# L298.net
KiCad netlist of a schematic drawn in Altium Designer
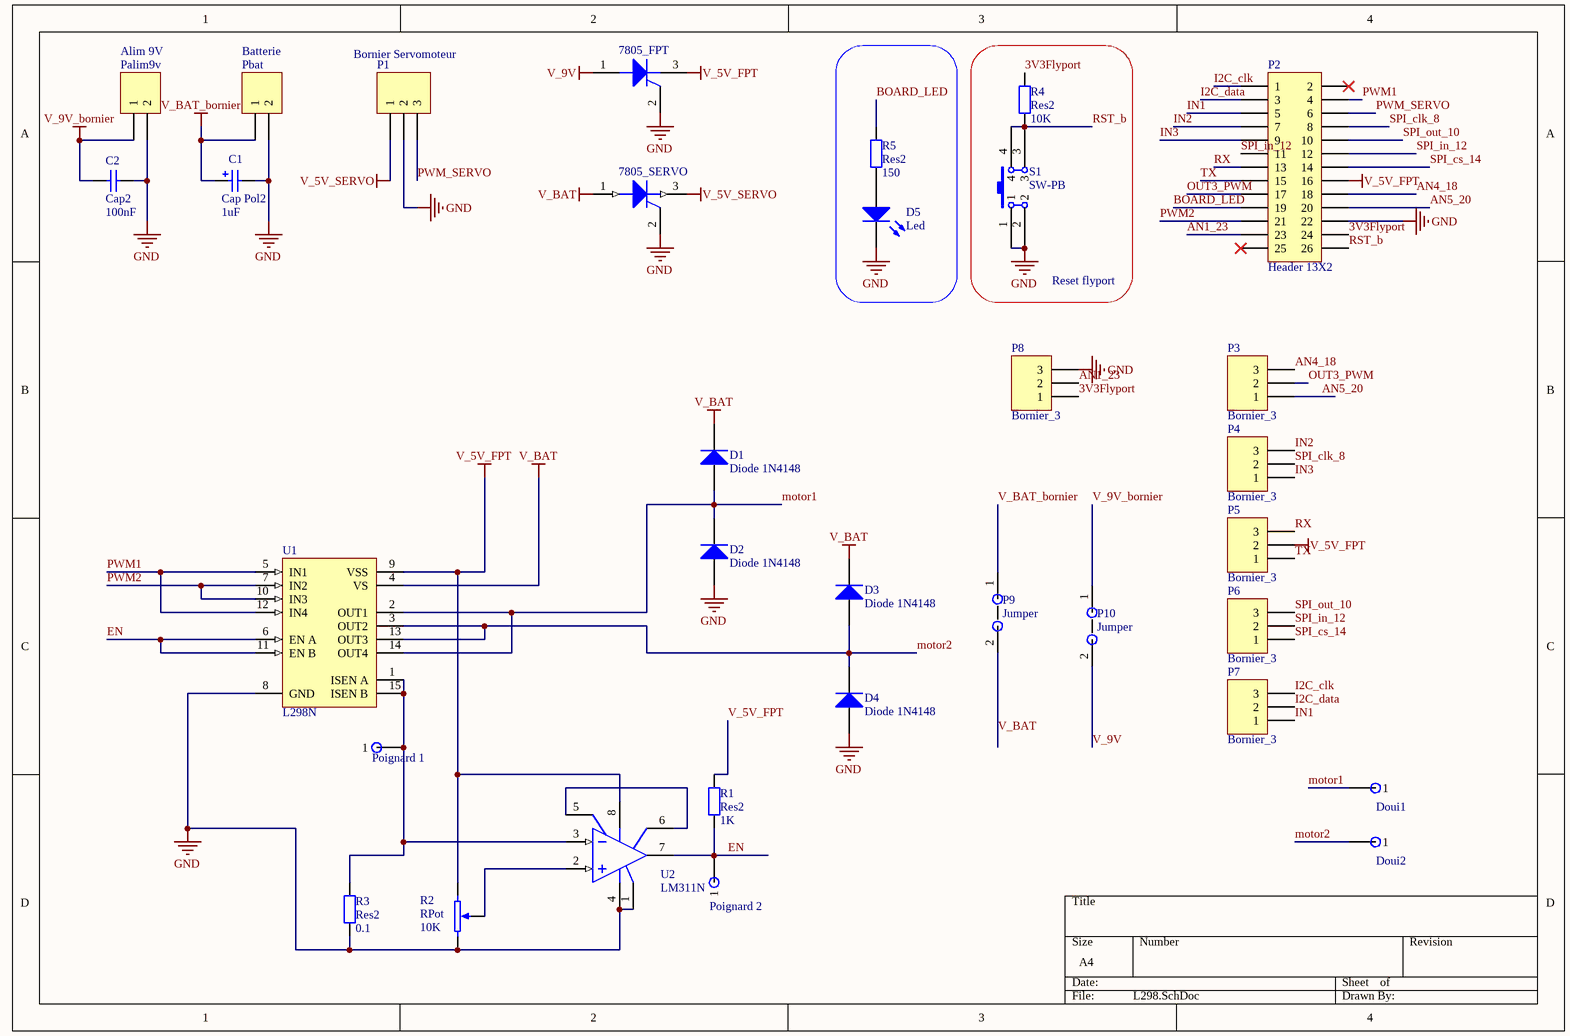
[diagram p0: L298.SchDoc]

(export (version "E")
  (design (tool "Eeschema 10.0.6"))
  (components
    (comp (ref "7805_FPT")
      (value "SCR")
      (footprint "TO-220-AB")
      (description "Silicon Controlled Rectifier")
      (fields (field (name "PUBLISHER") "Altium Limited"))
      (libsource (lib "Miscellaneous Devices") (part "SCR"))
    )
    (comp (ref "7805_SERVO")
      (value "SCR")
      (footprint "TO-220-AB")
      (description "Silicon Controlled Rectifier")
      (fields (field (name "PUBLISHER") "Altium Limited"))
      (libsource (lib "Miscellaneous Devices") (part "SCR"))
    )
    (comp (ref "C1")
      (value "Cap Pol2")
      (footprint "Capa2_pol")
      (description "Polarized Capacitor (Radial)")
      (fields (field (name "ALTIUM_VALUE") "1uF") (field (name "PUBLISHER") "Altium Limited"))
      (libsource (lib "LIBRAIRIE_INTEGREE_PHELMA1") (part "Cap Pol2"))
    )
    (comp (ref "C2")
      (value "Cap2")
      (footprint "CAPA2")
      (description "Capacitor")
      (fields (field (name "ALTIUM_VALUE") "100nF") (field (name "PUBLISHER") "Altium Limited"))
      (libsource (lib "LIBRAIRIE_INTEGREE_PHELMA1") (part "Cap2"))
    )
    (comp (ref "D1")
      (value "Diode 1N4148")
      (footprint "Ddiode")
      (description "High Conductance Fast Diode")
      (fields (field (name "PUBLISHER") "Altium Limited"))
      (libsource (lib "LIBRAIRIE_INTEGREE_PHELMA1") (part "Diode 1N4148"))
    )
    (comp (ref "D2")
      (value "Diode 1N4148")
      (footprint "Ddiode")
      (description "High Conductance Fast Diode")
      (fields (field (name "PUBLISHER") "Altium Limited"))
      (libsource (lib "LIBRAIRIE_INTEGREE_PHELMA1") (part "Diode 1N4148"))
    )
    (comp (ref "D3")
      (value "Diode 1N4148")
      (footprint "Ddiode")
      (description "High Conductance Fast Diode")
      (fields (field (name "PUBLISHER") "Altium Limited"))
      (libsource (lib "LIBRAIRIE_INTEGREE_PHELMA1") (part "Diode 1N4148"))
    )
    (comp (ref "D4")
      (value "Diode 1N4148")
      (footprint "Ddiode")
      (description "High Conductance Fast Diode")
      (fields (field (name "PUBLISHER") "Altium Limited"))
      (libsource (lib "LIBRAIRIE_INTEGREE_PHELMA1") (part "Diode 1N4148"))
    )
    (comp (ref "D5")
      (value "Led")
      (footprint "LED")
      (description "LED")
      (fields (field (name "PUBLISHER") "Altium Limited"))
      (libsource (lib "LIBRAIRIE_INTEGREE_PHELMA1") (part "Led"))
    )
    (comp (ref "Doui1")
      (value "douille_2mm")
      (footprint "Douille-2mm")
      (description "1-Pin")
      (fields (field (name "PUBLISHER") "Altium Limited"))
      (libsource (lib "INTEGRATED_LIBRARY1_CONNECTEURS") (part "douille_2mm"))
    )
    (comp (ref "Doui2")
      (value "douille_2mm")
      (footprint "Douille-2mm")
      (description "1-Pin")
      (fields (field (name "PUBLISHER") "Altium Limited"))
      (libsource (lib "INTEGRATED_LIBRARY1_CONNECTEURS") (part "douille_2mm"))
    )
    (comp (ref "P1")
      (value "Bornier Servomoteur")
      (footprint "Bornier_3")
      (description "Header, 3-Pin")
      (fields (field (name "PUBLISHER") "Altium Limited"))
      (libsource (lib "") (part "Bornier_3_1"))
    )
    (comp (ref "P2")
      (value "Header 13X2")
      (footprint "HDR2X13")
      (description "Header, 13-Pin, Dual row")
      (fields (field (name "PUBLISHER") "Altium Limited"))
      (libsource (lib "Miscellaneous Connectors") (part "Header 13X2"))
    )
    (comp (ref "P3")
      (value "Bornier_3")
      (footprint "Bornier_3")
      (description "Header, 3-Pin")
      (fields (field (name "PUBLISHER") "Altium Limited"))
      (libsource (lib "INTEGRATED_LIBRARY1_CONNECTEURS") (part "Bornier_3"))
    )
    (comp (ref "P4")
      (value "Bornier_3")
      (footprint "Bornier_3")
      (description "Header, 3-Pin")
      (fields (field (name "PUBLISHER") "Altium Limited"))
      (libsource (lib "INTEGRATED_LIBRARY1_CONNECTEURS") (part "Bornier_3"))
    )
    (comp (ref "P5")
      (value "Bornier_3")
      (footprint "Bornier_3")
      (description "Header, 3-Pin")
      (fields (field (name "PUBLISHER") "Altium Limited"))
      (libsource (lib "INTEGRATED_LIBRARY1_CONNECTEURS") (part "Bornier_3"))
    )
    (comp (ref "P6")
      (value "Bornier_3")
      (footprint "Bornier_3")
      (description "Header, 3-Pin")
      (fields (field (name "PUBLISHER") "Altium Limited"))
      (libsource (lib "INTEGRATED_LIBRARY1_CONNECTEURS") (part "Bornier_3"))
    )
    (comp (ref "P7")
      (value "Bornier_3")
      (footprint "Bornier_3")
      (description "Header, 3-Pin")
      (fields (field (name "PUBLISHER") "Altium Limited"))
      (libsource (lib "INTEGRATED_LIBRARY1_CONNECTEURS") (part "Bornier_3"))
    )
    (comp (ref "P8")
      (value "Bornier_3")
      (footprint "Bornier_3")
      (description "Header, 3-Pin")
      (fields (field (name "PUBLISHER") "Altium Limited"))
      (libsource (lib "INTEGRATED_LIBRARY1_CONNECTEURS") (part "Bornier_3"))
    )
    (comp (ref "P9")
      (value "Jumper")
      (footprint "picot2")
      (fields (field (name "PUBLISHER") "Altium Limited"))
      (libsource (lib "INTEGRATED_LIBRARY1_CONNECTEURS") (part "Jumper"))
    )
    (comp (ref "P10")
      (value "Jumper")
      (footprint "picot2")
      (fields (field (name "PUBLISHER") "Altium Limited"))
      (libsource (lib "INTEGRATED_LIBRARY1_CONNECTEURS") (part "Jumper"))
    )
    (comp (ref "Palim9v")
      (value "Alim 9V")
      (footprint "Bornier_2")
      (description "Header, 2-Pin")
      (fields (field (name "PUBLISHER") "Altium Limited"))
      (libsource (lib "INTEGRATED_LIBRARY1_CONNECTEURS") (part "Bornier_2"))
    )
    (comp (ref "Pbat")
      (value "Batterie")
      (footprint "Bornier_2")
      (description "Header, 2-Pin")
      (fields (field (name "PUBLISHER") "Altium Limited"))
      (libsource (lib "INTEGRATED_LIBRARY1_CONNECTEURS") (part "Bornier_2"))
    )
    (comp (ref "Poignard 1")
      (value "Poignard")
      (footprint "Poignard")
      (fields (field (name "PUBLISHER") "Altium Limited"))
      (libsource (lib "INTEGRATED_LIBRARY1_CONNECTEURS") (part "Poignard"))
    )
    (comp (ref "Poignard 2")
      (value "Poignard")
      (footprint "Poignard")
      (fields (field (name "PUBLISHER") "Altium Limited"))
      (libsource (lib "INTEGRATED_LIBRARY1_CONNECTEURS") (part "Poignard"))
    )
    (comp (ref "R1")
      (value "Res2")
      (footprint "res5_1/4W")
      (description "Resistor")
      (fields (field (name "ALTIUM_VALUE") "1K") (field (name "PUBLISHER") "Altium Limited"))
      (libsource (lib "") (part "Res2_1"))
    )
    (comp (ref "R2")
      (value "RPot")
      (footprint "AJUSTABLE")
      (description "Potentiometer")
      (fields (field (name "ALTIUM_VALUE") "10K") (field (name "PUBLISHER") "Altium Limited"))
      (libsource (lib "LIBRAIRIE_INTEGREE_PHELMA1") (part "RPot"))
    )
    (comp (ref "R3")
      (value "Res2")
      (footprint "res5_1/4W")
      (description "Resistor")
      (fields (field (name "ALTIUM_VALUE") "0.1") (field (name "PUBLISHER") "Altium Limited"))
      (libsource (lib "LIBRAIRIE_INTEGREE_PHELMA1") (part "Res2"))
    )
    (comp (ref "R4")
      (value "Res2")
      (footprint "res5_1/4W")
      (description "Resistor")
      (fields (field (name "ALTIUM_VALUE") "10K") (field (name "PUBLISHER") "Altium Limited"))
      (libsource (lib "LIBRAIRIE_INTEGREE_PHELMA1") (part "Res2"))
    )
    (comp (ref "R5")
      (value "Res2")
      (footprint "res5_1/4W")
      (description "Resistor")
      (fields (field (name "ALTIUM_VALUE") "150") (field (name "PUBLISHER") "Altium Limited"))
      (libsource (lib "LIBRAIRIE_INTEGREE_PHELMA1") (part "Res2"))
    )
    (comp (ref "S1")
      (value "SW-PB")
      (footprint "SW_BP")
      (description "Switch")
      (fields (field (name "PUBLISHER") "Altium Limited"))
      (libsource (lib "INTEGRATED_LIBRARY1_CONNECTEURS") (part "SW-PB"))
    )
    (comp (ref "U1")
      (value "L298N")
      (footprint "Multiwatt15V")
      (description "Dual Full Bridge Driver")
      (fields (field (name "PUBLISHER") "Altium Limited"))
      (libsource (lib "ST Interface DC Motor Controller") (part "L298N"))
    )
    (comp (ref "U2")
      (value "LM311N")
      (footprint "LIBRAIRIE_INTEGREE_PHELMA1:DIP8")
      (description "Voltage Comparator")
      (fields (field (name "PUBLISHER") "Altium Limited"))
      (libsource (lib "LIBRAIRIE_INTEGREE_PHELMA1") (part "LM311N"))
    )
  )
  (nets
    (net (code "1") (name "/3V3Flyport") (class "Default")
      (node (ref "P2") (pin "24") (pinfunction "24_24") (pintype "passive"))
      (node (ref "P8") (pin "1") (pinfunction "1_1") (pintype "passive"))
      (node (ref "R4") (pin "1") (pinfunction "1_1") (pintype "passive"))
    )
    (net (code "2") (name "/AN1_23") (class "Default")
      (node (ref "P2") (pin "23") (pinfunction "23_23") (pintype "passive"))
      (node (ref "P8") (pin "2") (pinfunction "2_2") (pintype "passive"))
    )
    (net (code "3") (name "/AN4_18") (class "Default")
      (node (ref "P2") (pin "18") (pinfunction "18_18") (pintype "passive"))
      (node (ref "P3") (pin "3") (pinfunction "3_3") (pintype "passive"))
    )
    (net (code "4") (name "/AN5_20") (class "Default")
      (node (ref "P2") (pin "20") (pinfunction "20_20") (pintype "passive"))
      (node (ref "P3") (pin "1") (pinfunction "1_1") (pintype "passive"))
    )
    (net (code "5") (name "/BOARD_LED") (class "Default")
      (node (ref "P2") (pin "19") (pinfunction "19_19") (pintype "passive"))
      (node (ref "R5") (pin "1") (pinfunction "1_1") (pintype "passive"))
    )
    (net (code "6") (name "/EN") (class "Default")
      (node (ref "Poignard 2") (pin "1") (pinfunction "1_1") (pintype "passive"))
      (node (ref "R1") (pin "1") (pinfunction "1_1") (pintype "passive"))
      (node (ref "U1") (pin "11") (pinfunction "EN_B_11") (pintype "input"))
      (node (ref "U1") (pin "6") (pinfunction "EN_A_6") (pintype "input"))
      (node (ref "U2") (pin "7") (pinfunction "OUT_7") (pintype "open_collector"))
    )
    (net (code "7") (name "/I2C_clk") (class "Default")
      (node (ref "P2") (pin "1") (pinfunction "1_1") (pintype "passive"))
      (node (ref "P7") (pin "3") (pinfunction "3_3") (pintype "passive"))
    )
    (net (code "8") (name "/I2C_data") (class "Default")
      (node (ref "P2") (pin "3") (pinfunction "3_3") (pintype "passive"))
      (node (ref "P7") (pin "2") (pinfunction "2_2") (pintype "passive"))
    )
    (net (code "9") (name "/IN1") (class "Default")
      (node (ref "P2") (pin "5") (pinfunction "5_5") (pintype "passive"))
      (node (ref "P7") (pin "1") (pinfunction "1_1") (pintype "passive"))
    )
    (net (code "10") (name "/IN2") (class "Default")
      (node (ref "P2") (pin "7") (pinfunction "7_7") (pintype "passive"))
      (node (ref "P4") (pin "3") (pinfunction "3_3") (pintype "passive"))
    )
    (net (code "11") (name "/IN3") (class "Default")
      (node (ref "P2") (pin "9") (pinfunction "9_9") (pintype "passive"))
      (node (ref "P4") (pin "1") (pinfunction "1_1") (pintype "passive"))
    )
    (net (code "12") (name "/OUT3_PWM") (class "Default")
      (node (ref "P2") (pin "17") (pinfunction "17_17") (pintype "passive"))
      (node (ref "P3") (pin "2") (pinfunction "2_2") (pintype "passive"))
    )
    (net (code "13") (name "/PWM1") (class "Default")
      (node (ref "P2") (pin "4") (pinfunction "4_4") (pintype "passive"))
      (node (ref "U1") (pin "12") (pinfunction "IN4_12") (pintype "input"))
      (node (ref "U1") (pin "5") (pinfunction "IN1_5") (pintype "input"))
    )
    (net (code "14") (name "/PWM2") (class "Default")
      (node (ref "P2") (pin "21") (pinfunction "21_21") (pintype "passive"))
      (node (ref "U1") (pin "10") (pinfunction "IN3_10") (pintype "input"))
      (node (ref "U1") (pin "7") (pinfunction "IN2_7") (pintype "input"))
    )
    (net (code "15") (name "/PWM_SERVO") (class "Default")
      (node (ref "P1") (pin "3") (pinfunction "3_3") (pintype "passive"))
      (node (ref "P2") (pin "6") (pinfunction "6_6") (pintype "passive"))
    )
    (net (code "16") (name "/RST_b") (class "Default")
      (node (ref "P2") (pin "26") (pinfunction "26_26") (pintype "passive"))
      (node (ref "R4") (pin "2") (pinfunction "2_2") (pintype "passive"))
      (node (ref "S1") (pin "3") (pinfunction "3_3") (pintype "passive"))
      (node (ref "S1") (pin "4") (pinfunction "4_4") (pintype "passive"))
    )
    (net (code "17") (name "/RX") (class "Default")
      (node (ref "P2") (pin "13") (pinfunction "13_13") (pintype "passive"))
      (node (ref "P5") (pin "3") (pinfunction "3_3") (pintype "passive"))
    )
    (net (code "18") (name "/SPI_clk_8") (class "Default")
      (node (ref "P2") (pin "8") (pinfunction "8_8") (pintype "passive"))
      (node (ref "P4") (pin "2") (pinfunction "2_2") (pintype "passive"))
    )
    (net (code "19") (name "/SPI_cs_14") (class "Default")
      (node (ref "P2") (pin "14") (pinfunction "14_14") (pintype "passive"))
      (node (ref "P6") (pin "1") (pinfunction "1_1") (pintype "passive"))
    )
    (net (code "20") (name "/SPI_in_12") (class "Default")
      (node (ref "P2") (pin "11") (pinfunction "11_11") (pintype "passive"))
      (node (ref "P2") (pin "12") (pinfunction "12_12") (pintype "passive"))
      (node (ref "P6") (pin "2") (pinfunction "2_2") (pintype "passive"))
    )
    (net (code "21") (name "/SPI_out_10") (class "Default")
      (node (ref "P2") (pin "10") (pinfunction "10_10") (pintype "passive"))
      (node (ref "P6") (pin "3") (pinfunction "3_3") (pintype "passive"))
    )
    (net (code "22") (name "/TX") (class "Default")
      (node (ref "P2") (pin "15") (pinfunction "15_15") (pintype "passive"))
      (node (ref "P5") (pin "1") (pinfunction "1_1") (pintype "passive"))
    )
    (net (code "23") (name "/motor1") (class "Default")
      (node (ref "D1") (pin "1") (pinfunction "A_1") (pintype "passive"))
      (node (ref "D2") (pin "2") (pinfunction "K_2") (pintype "passive"))
      (node (ref "Doui1") (pin "1") (pinfunction "1_1") (pintype "passive"))
      (node (ref "U1") (pin "14") (pinfunction "OUT4_14") (pintype "passive"))
      (node (ref "U1") (pin "2") (pinfunction "OUT1_2") (pintype "passive"))
    )
    (net (code "24") (name "/motor2") (class "Default")
      (node (ref "D3") (pin "1") (pinfunction "A_1") (pintype "passive"))
      (node (ref "D4") (pin "2") (pinfunction "K_2") (pintype "passive"))
      (node (ref "Doui2") (pin "1") (pinfunction "1_1") (pintype "passive"))
      (node (ref "U1") (pin "13") (pinfunction "OUT3_13") (pintype "passive"))
      (node (ref "U1") (pin "3") (pinfunction "OUT2_3") (pintype "passive"))
    )
    (net (code "25") (name "GND") (class "Default")
      (node (ref "7805_FPT") (pin "2") (pinfunction "GND_2") (pintype "power_in"))
      (node (ref "7805_SERVO") (pin "2") (pinfunction "GND_2") (pintype "power_in"))
      (node (ref "C1") (pin "2") (pinfunction "2_2") (pintype "passive"))
      (node (ref "C2") (pin "2") (pinfunction "2_2") (pintype "passive"))
      (node (ref "D2") (pin "1") (pinfunction "A_1") (pintype "passive"))
      (node (ref "D4") (pin "1") (pinfunction "A_1") (pintype "passive"))
      (node (ref "D5") (pin "2") (pinfunction "K_2") (pintype "passive"))
      (node (ref "P1") (pin "2") (pinfunction "2_2") (pintype "passive"))
      (node (ref "P2") (pin "22") (pinfunction "22_22") (pintype "passive"))
      (node (ref "P8") (pin "3") (pinfunction "3_3") (pintype "passive"))
      (node (ref "Palim9v") (pin "2") (pinfunction "2_2") (pintype "passive"))
      (node (ref "Pbat") (pin "2") (pinfunction "2_2") (pintype "passive"))
      (node (ref "R2") (pin "3") (pinfunction "TOP_3") (pintype "passive"))
      (node (ref "R3") (pin "2") (pinfunction "2_2") (pintype "passive"))
      (node (ref "S1") (pin "1") (pinfunction "1_1") (pintype "passive"))
      (node (ref "S1") (pin "2") (pinfunction "2_2") (pintype "passive"))
      (node (ref "U1") (pin "8") (pinfunction "GND_8") (pintype "power_in"))
      (node (ref "U2") (pin "1") (pinfunction "GND_1") (pintype "power_in"))
      (node (ref "U2") (pin "4") (pinfunction "V-_(CASE)_4") (pintype "power_in"))
    )
    (net (code "26") (name "Net-(D5-A)") (class "Default")
      (node (ref "D5") (pin "1") (pinfunction "A_1") (pintype "passive"))
      (node (ref "R5") (pin "2") (pinfunction "2_2") (pintype "passive"))
    )
    (net (code "27") (name "Net-(R2-TAP)") (class "Default")
      (node (ref "R2") (pin "2") (pinfunction "TAP_2") (pintype "passive"))
      (node (ref "U2") (pin "2") (pinfunction "IN+_2") (pintype "input"))
    )
    (net (code "28") (name "Net-(U1-ISEN_A)") (class "Default")
      (node (ref "Poignard 1") (pin "1") (pinfunction "1_1") (pintype "passive"))
      (node (ref "R3") (pin "1") (pinfunction "1_1") (pintype "passive"))
      (node (ref "U1") (pin "1") (pinfunction "ISEN_A_1") (pintype "passive"))
      (node (ref "U1") (pin "15") (pinfunction "ISEN_B_15") (pintype "passive"))
      (node (ref "U2") (pin "3") (pinfunction "IN-_3") (pintype "input"))
    )
    (net (code "29") (name "Net-(U2-BAL)") (class "Default")
      (node (ref "U2") (pin "5") (pinfunction "BAL_5") (pintype "passive"))
      (node (ref "U2") (pin "6") (pinfunction "BAL/STB_6") (pintype "passive"))
    )
    (net (code "30") (name "V_5V_FPT") (class "Default")
      (node (ref "7805_FPT") (pin "3") (pinfunction "OUT_3") (pintype "power_in"))
      (node (ref "P2") (pin "16") (pinfunction "16_16") (pintype "passive"))
      (node (ref "P5") (pin "2") (pinfunction "2_2") (pintype "passive"))
      (node (ref "R1") (pin "2") (pinfunction "2_2") (pintype "passive"))
      (node (ref "R2") (pin "1") (pinfunction "BOT_1") (pintype "passive"))
      (node (ref "U1") (pin "9") (pinfunction "VSS_9") (pintype "power_in"))
      (node (ref "U2") (pin "8") (pinfunction "V+_8") (pintype "power_in"))
    )
    (net (code "31") (name "V_5V_SERVO") (class "Default")
      (node (ref "7805_SERVO") (pin "3") (pinfunction "OUT_3") (pintype "power_in"))
      (node (ref "P1") (pin "1") (pinfunction "1_1") (pintype "passive"))
    )
    (net (code "32") (name "V_9V") (class "Default")
      (node (ref "7805_FPT") (pin "1") (pinfunction "IN_1") (pintype "power_in"))
      (node (ref "P10") (pin "2") (pinfunction "2_2") (pintype "passive"))
    )
    (net (code "33") (name "V_9V_bornier") (class "Default")
      (node (ref "C2") (pin "1") (pinfunction "1_1") (pintype "passive"))
      (node (ref "P10") (pin "1") (pinfunction "1_1") (pintype "passive"))
      (node (ref "Palim9v") (pin "1") (pinfunction "1_1") (pintype "passive"))
    )
    (net (code "34") (name "V_BAT") (class "Default")
      (node (ref "7805_SERVO") (pin "1") (pinfunction "IN_1") (pintype "power_in"))
      (node (ref "D1") (pin "2") (pinfunction "K_2") (pintype "passive"))
      (node (ref "D3") (pin "2") (pinfunction "K_2") (pintype "passive"))
      (node (ref "P9") (pin "2") (pinfunction "2_2") (pintype "passive"))
      (node (ref "U1") (pin "4") (pinfunction "VS_4") (pintype "power_in"))
    )
    (net (code "35") (name "V_BAT_bornier") (class "Default")
      (node (ref "C1") (pin "1") (pinfunction "1_1") (pintype "passive"))
      (node (ref "P9") (pin "1") (pinfunction "1_1") (pintype "passive"))
      (node (ref "Pbat") (pin "1") (pinfunction "1_1") (pintype "passive"))
    )
    (net (code "36") (name "unconnected-(P2-Pad2)") (class "Default")
      (node (ref "P2") (pin "2") (pinfunction "2_2") (pintype "passive+no_connect"))
    )
    (net (code "37") (name "unconnected-(P2-Pad25)") (class "Default")
      (node (ref "P2") (pin "25") (pinfunction "25_25") (pintype "passive+no_connect"))
    )
  )
)
